# MCU.net
KiCad netlist of a schematic drawn in Altium Designer
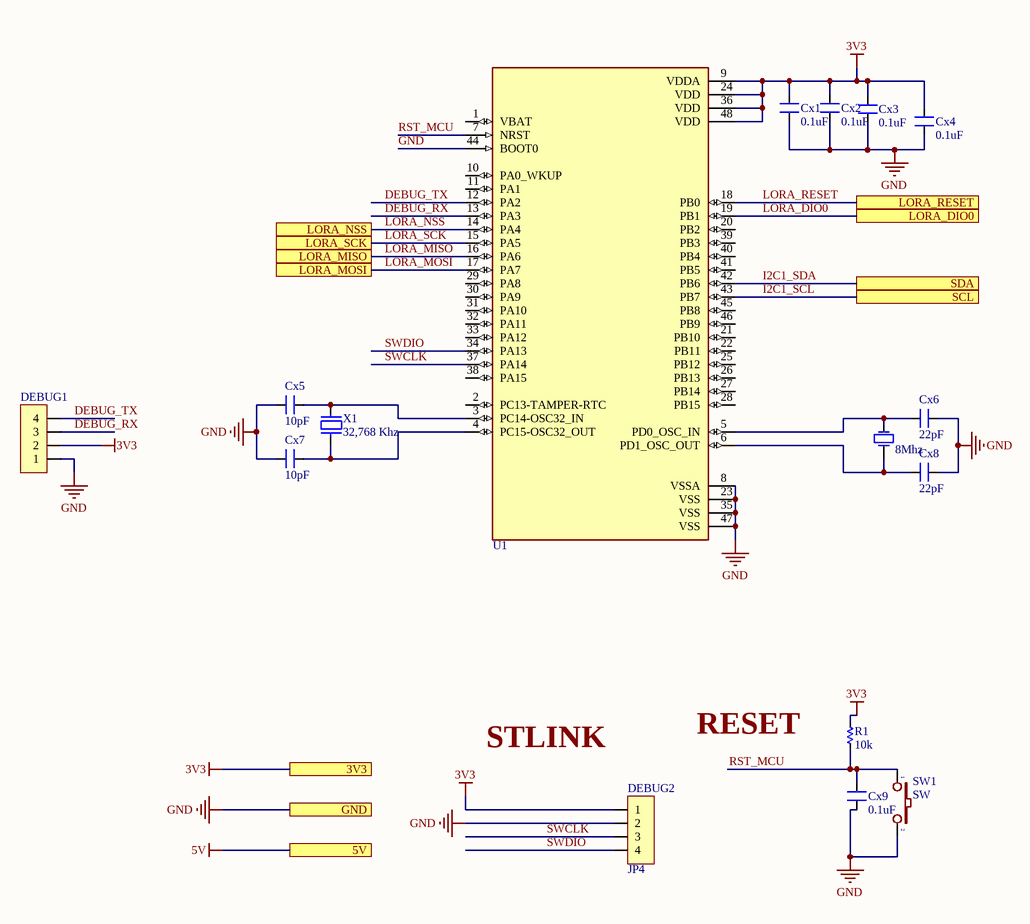
[diagram p0: MCU.SchDoc]

(export (version "E")
  (design (tool "Eeschema 10.0.6"))
  (components
    (comp (ref "Cx1") (value "0.1uF") (footprint "CN-SMD-0805") (libsource (lib "SensorV1") (part "CN")))
    (comp (ref "Cx2") (value "0.1uF") (footprint "CN-SMD-0805") (libsource (lib "SensorV1") (part "CN")))
    (comp (ref "Cx3") (value "0.1uF") (footprint "CN-SMD-0805") (libsource (lib "SensorV1") (part "CN")))
    (comp (ref "Cx4") (value "0.1uF") (footprint "CN-SMD-0805") (libsource (lib "SensorV1") (part "CN")))
    (comp (ref "Cx5")
      (value "10pF")
      (footprint "CN-SMD-0805")
      (description "recommended 12.5pF")
      (libsource (lib "SensorV1") (part "CN_2"))
    )
    (comp (ref "Cx6") (value "22pF") (footprint "CN-SMD-0805") (libsource (lib "SensorV1") (part "CN_5")))
    (comp (ref "Cx7")
      (value "10pF")
      (footprint "CN-SMD-0805")
      (description "recommended 12.5pF")
      (libsource (lib "SensorV1") (part "CN_2"))
    )
    (comp (ref "Cx8") (value "22pF") (footprint "CN-SMD-0805") (libsource (lib "SensorV1") (part "CN_5")))
    (comp (ref "Cx9") (value "0.1uF") (footprint "CN-SMD-0805") (libsource (lib "SensorV1") (part "CN")))
    (comp (ref "DEBUG1")
      (value "~")
      (footprint "JP4-C1T")
      (description "WR-PHD 2.54 mm Angled Socket Header")
      (fields
        (field (name "MANUFACTURER") "Würth Elektronik eiSos GmbH")
        (field (name "PARTNO") "613004143121")
        (field (name "CREATED BY") "Karrer Zheng")
      )
      (libsource (lib "SensorV1") (part "JP4"))
    )
    (comp (ref "DEBUG2")
      (value "JP4")
      (footprint "JP4-C1T")
      (description "WR-PHD 2.54 mm Angled Socket Header")
      (fields
        (field (name "MANUFACTURER") "Würth Elektronik eiSos GmbH")
        (field (name "PARTNO") "613004143121")
        (field (name "CREATED BY") "Karrer Zheng")
      )
      (libsource (lib "") (part "JP4_1"))
    )
    (comp (ref "R1")
      (value "10k")
      (footprint "RES-SMD-0805")
      (description "Resistor")
      (fields
        (field (name "MANUFACTURER") "Generic Components")
        (field (name "PUBLISHER") "Altium Hobart Technology Centre")
      )
      (libsource (lib "SensorV1") (part "Res-SMD"))
    )
    (comp (ref "SW1")
      (value "SW")
      (footprint "SW1-SMD")
      (description "Switch button 2 pin")
      (libsource (lib "SensorV1") (part "SW2"))
    )
    (comp (ref "U1")
      (value "STM32")
      (footprint "LQFP48_L")
      (description "STM32 ARM-based 32-bit MCU with 64 Kbytes Flash, 64-pin LQFP, Industrial Temperature")
      (libsource (lib "SolarV1") (part "STM32F103C8T6"))
    )
    (comp (ref "X1")
      (value "32,768 Khz")
      (footprint "XT32kn")
      (description "Crystal 32,768kHz for timer real")
      (libsource (lib "GPS_Traking_V1_1") (part "XT32k"))
    )
    (comp (ref "Y1")
      (value "8Mhz")
      (footprint "XT2")
      (description "Cắm")
      (libsource (lib "khue") (part "Thach Anh 8Mhz DIP"))
    )
  )
  (nets
    (net (code "1") (name "/DEBUG_RX") (class "Default")
      (node (ref "DEBUG1") (pin "3") (pinfunction "3_3") (pintype "passive"))
      (node (ref "U1") (pin "13") (pinfunction "PA3_13") (pintype "bidirectional"))
    )
    (net (code "2") (name "/DEBUG_TX") (class "Default")
      (node (ref "DEBUG1") (pin "4") (pinfunction "4_4") (pintype "passive"))
      (node (ref "U1") (pin "12") (pinfunction "PA2_12") (pintype "bidirectional"))
    )
    (net (code "3") (name "/I2C1_SCL") (class "Default")
      (node (ref "U1") (pin "43") (pinfunction "PB7_43") (pintype "bidirectional"))
    )
    (net (code "4") (name "/I2C1_SDA") (class "Default")
      (node (ref "U1") (pin "42") (pinfunction "PB6_42") (pintype "bidirectional"))
    )
    (net (code "5") (name "/LORA_DIO0") (class "Default")
      (node (ref "U1") (pin "19") (pinfunction "PB1_19") (pintype "bidirectional"))
    )
    (net (code "6") (name "/LORA_MISO") (class "Default")
      (node (ref "U1") (pin "16") (pinfunction "PA6_16") (pintype "bidirectional"))
    )
    (net (code "7") (name "/LORA_MOSI") (class "Default")
      (node (ref "U1") (pin "17") (pinfunction "PA7_17") (pintype "bidirectional"))
    )
    (net (code "8") (name "/LORA_NSS") (class "Default")
      (node (ref "U1") (pin "14") (pinfunction "PA4_14") (pintype "bidirectional"))
    )
    (net (code "9") (name "/LORA_RESET") (class "Default")
      (node (ref "U1") (pin "18") (pinfunction "PB0_18") (pintype "bidirectional"))
    )
    (net (code "10") (name "/LORA_SCK") (class "Default")
      (node (ref "U1") (pin "15") (pinfunction "PA5_15") (pintype "bidirectional"))
    )
    (net (code "11") (name "/RST_MCU") (class "Default")
      (node (ref "Cx9") (pin "2") (pinfunction "2_2") (pintype "passive"))
      (node (ref "R1") (pin "2") (pinfunction "2_2") (pintype "passive"))
      (node (ref "SW1") (pin "1") (pinfunction "1_1") (pintype "passive"))
      (node (ref "U1") (pin "7") (pinfunction "NRST_7") (pintype "input"))
    )
    (net (code "12") (name "/SWCLK") (class "Default")
      (node (ref "DEBUG2") (pin "3") (pinfunction "3_3") (pintype "passive"))
      (node (ref "U1") (pin "37") (pinfunction "PA14_37") (pintype "bidirectional"))
    )
    (net (code "13") (name "/SWDIO") (class "Default")
      (node (ref "DEBUG2") (pin "4") (pinfunction "4_4") (pintype "passive"))
      (node (ref "U1") (pin "34") (pinfunction "PA13_34") (pintype "bidirectional"))
    )
    (net (code "14") (name "3V3") (class "Default")
      (node (ref "Cx1") (pin "2") (pinfunction "2_2") (pintype "passive"))
      (node (ref "Cx2") (pin "2") (pinfunction "2_2") (pintype "passive"))
      (node (ref "Cx3") (pin "2") (pinfunction "2_2") (pintype "passive"))
      (node (ref "Cx4") (pin "2") (pinfunction "2_2") (pintype "passive"))
      (node (ref "DEBUG1") (pin "2") (pinfunction "2_2") (pintype "passive"))
      (node (ref "DEBUG2") (pin "1") (pinfunction "1_1") (pintype "passive"))
      (node (ref "R1") (pin "1") (pinfunction "1_1") (pintype "passive"))
      (node (ref "U1") (pin "24") (pinfunction "VDD_24") (pintype "power_in"))
      (node (ref "U1") (pin "36") (pinfunction "VDD_36") (pintype "power_in"))
      (node (ref "U1") (pin "48") (pinfunction "VDD_48") (pintype "power_in"))
      (node (ref "U1") (pin "9") (pinfunction "VDDA_9") (pintype "power_in"))
    )
    (net (code "16") (name "GND") (class "Default")
      (node (ref "Cx1") (pin "1") (pinfunction "1_1") (pintype "passive"))
      (node (ref "Cx2") (pin "1") (pinfunction "1_1") (pintype "passive"))
      (node (ref "Cx3") (pin "1") (pinfunction "1_1") (pintype "passive"))
      (node (ref "Cx4") (pin "1") (pinfunction "1_1") (pintype "passive"))
      (node (ref "Cx5") (pin "1") (pinfunction "1_1") (pintype "passive"))
      (node (ref "Cx6") (pin "2") (pinfunction "2_2") (pintype "passive"))
      (node (ref "Cx7") (pin "1") (pinfunction "1_1") (pintype "passive"))
      (node (ref "Cx8") (pin "2") (pinfunction "2_2") (pintype "passive"))
      (node (ref "Cx9") (pin "1") (pinfunction "1_1") (pintype "passive"))
      (node (ref "DEBUG1") (pin "1") (pinfunction "1_1") (pintype "passive"))
      (node (ref "DEBUG2") (pin "2") (pinfunction "2_2") (pintype "passive"))
      (node (ref "SW1") (pin "2") (pinfunction "2_2") (pintype "passive"))
      (node (ref "U1") (pin "23") (pinfunction "VSS_23") (pintype "power_in"))
      (node (ref "U1") (pin "35") (pinfunction "VSS_35") (pintype "power_in"))
      (node (ref "U1") (pin "44") (pinfunction "BOOT0_44") (pintype "input"))
      (node (ref "U1") (pin "47") (pinfunction "VSS_47") (pintype "power_in"))
      (node (ref "U1") (pin "8") (pinfunction "VSSA_8") (pintype "power_in"))
    )
    (net (code "17") (name "Net-(U1-PC14-OSC32_IN)") (class "Default")
      (node (ref "Cx5") (pin "2") (pinfunction "2_2") (pintype "passive"))
      (node (ref "U1") (pin "3") (pinfunction "PC14-OSC32_IN_3") (pintype "bidirectional"))
      (node (ref "X1") (pin "2") (pinfunction "2_2") (pintype "passive"))
    )
    (net (code "18") (name "Net-(U1-PC15-OSC32_OUT)") (class "Default")
      (node (ref "Cx7") (pin "2") (pinfunction "2_2") (pintype "passive"))
      (node (ref "U1") (pin "4") (pinfunction "PC15-OSC32_OUT_4") (pintype "bidirectional"))
      (node (ref "X1") (pin "1") (pinfunction "1_1") (pintype "passive"))
    )
    (net (code "19") (name "Net-(U1-PD0_OSC_IN)") (class "Default")
      (node (ref "Cx6") (pin "1") (pinfunction "1_1") (pintype "passive"))
      (node (ref "U1") (pin "5") (pinfunction "PD0_OSC_IN_5") (pintype "bidirectional"))
      (node (ref "Y1") (pin "1") (pinfunction "OSC1_1") (pintype "passive"))
    )
    (net (code "20") (name "Net-(U1-PD1_OSC_OUT)") (class "Default")
      (node (ref "Cx8") (pin "1") (pinfunction "1_1") (pintype "passive"))
      (node (ref "U1") (pin "6") (pinfunction "PD1_OSC_OUT_6") (pintype "bidirectional"))
      (node (ref "Y1") (pin "2") (pinfunction "OSC2_2") (pintype "passive"))
    )
    (net (code "21") (name "unconnected-(U1-PA0_WKUP-Pad10)") (class "Default")
      (node (ref "U1") (pin "10") (pinfunction "PA0_WKUP_10") (pintype "bidirectional"))
    )
    (net (code "22") (name "unconnected-(U1-PA1-Pad11)") (class "Default")
      (node (ref "U1") (pin "11") (pinfunction "PA1_11") (pintype "bidirectional"))
    )
    (net (code "23") (name "unconnected-(U1-PA8-Pad29)") (class "Default")
      (node (ref "U1") (pin "29") (pinfunction "PA8_29") (pintype "bidirectional"))
    )
    (net (code "24") (name "unconnected-(U1-PA9-Pad30)") (class "Default")
      (node (ref "U1") (pin "30") (pinfunction "PA9_30") (pintype "bidirectional"))
    )
    (net (code "25") (name "unconnected-(U1-PA10-Pad31)") (class "Default")
      (node (ref "U1") (pin "31") (pinfunction "PA10_31") (pintype "bidirectional"))
    )
    (net (code "26") (name "unconnected-(U1-PA11-Pad32)") (class "Default")
      (node (ref "U1") (pin "32") (pinfunction "PA11_32") (pintype "bidirectional"))
    )
    (net (code "27") (name "unconnected-(U1-PA12-Pad33)") (class "Default")
      (node (ref "U1") (pin "33") (pinfunction "PA12_33") (pintype "bidirectional"))
    )
    (net (code "28") (name "unconnected-(U1-PA15-Pad38)") (class "Default")
      (node (ref "U1") (pin "38") (pinfunction "PA15_38") (pintype "bidirectional"))
    )
    (net (code "29") (name "unconnected-(U1-PB2-Pad20)") (class "Default")
      (node (ref "U1") (pin "20") (pinfunction "PB2_20") (pintype "bidirectional"))
    )
    (net (code "30") (name "unconnected-(U1-PB3-Pad39)") (class "Default")
      (node (ref "U1") (pin "39") (pinfunction "PB3_39") (pintype "bidirectional"))
    )
    (net (code "31") (name "unconnected-(U1-PB4-Pad40)") (class "Default")
      (node (ref "U1") (pin "40") (pinfunction "PB4_40") (pintype "bidirectional"))
    )
    (net (code "32") (name "unconnected-(U1-PB5-Pad41)") (class "Default")
      (node (ref "U1") (pin "41") (pinfunction "PB5_41") (pintype "bidirectional"))
    )
    (net (code "33") (name "unconnected-(U1-PB8-Pad45)") (class "Default")
      (node (ref "U1") (pin "45") (pinfunction "PB8_45") (pintype "bidirectional"))
    )
    (net (code "34") (name "unconnected-(U1-PB9-Pad46)") (class "Default")
      (node (ref "U1") (pin "46") (pinfunction "PB9_46") (pintype "bidirectional"))
    )
    (net (code "35") (name "unconnected-(U1-PB10-Pad21)") (class "Default")
      (node (ref "U1") (pin "21") (pinfunction "PB10_21") (pintype "bidirectional"))
    )
    (net (code "36") (name "unconnected-(U1-PB11-Pad22)") (class "Default")
      (node (ref "U1") (pin "22") (pinfunction "PB11_22") (pintype "bidirectional"))
    )
    (net (code "37") (name "unconnected-(U1-PB12-Pad25)") (class "Default")
      (node (ref "U1") (pin "25") (pinfunction "PB12_25") (pintype "bidirectional"))
    )
    (net (code "38") (name "unconnected-(U1-PB13-Pad26)") (class "Default")
      (node (ref "U1") (pin "26") (pinfunction "PB13_26") (pintype "bidirectional"))
    )
    (net (code "39") (name "unconnected-(U1-PB14-Pad27)") (class "Default")
      (node (ref "U1") (pin "27") (pinfunction "PB14_27") (pintype "bidirectional"))
    )
    (net (code "40") (name "unconnected-(U1-PB15-Pad28)") (class "Default")
      (node (ref "U1") (pin "28") (pinfunction "PB15_28") (pintype "bidirectional"))
    )
    (net (code "41") (name "unconnected-(U1-PC13-TAMPER-RTC-Pad2)") (class "Default")
      (node (ref "U1") (pin "2") (pinfunction "PC13-TAMPER-RTC_2") (pintype "bidirectional"))
    )
    (net (code "42") (name "unconnected-(U1-VBAT-Pad1)") (class "Default")
      (node (ref "U1") (pin "1") (pinfunction "VBAT_1") (pintype "bidirectional"))
    )
  )
)
